# saklar_not_sentuhan.net
KiCad netlist of a schematic drawn in EAGLE
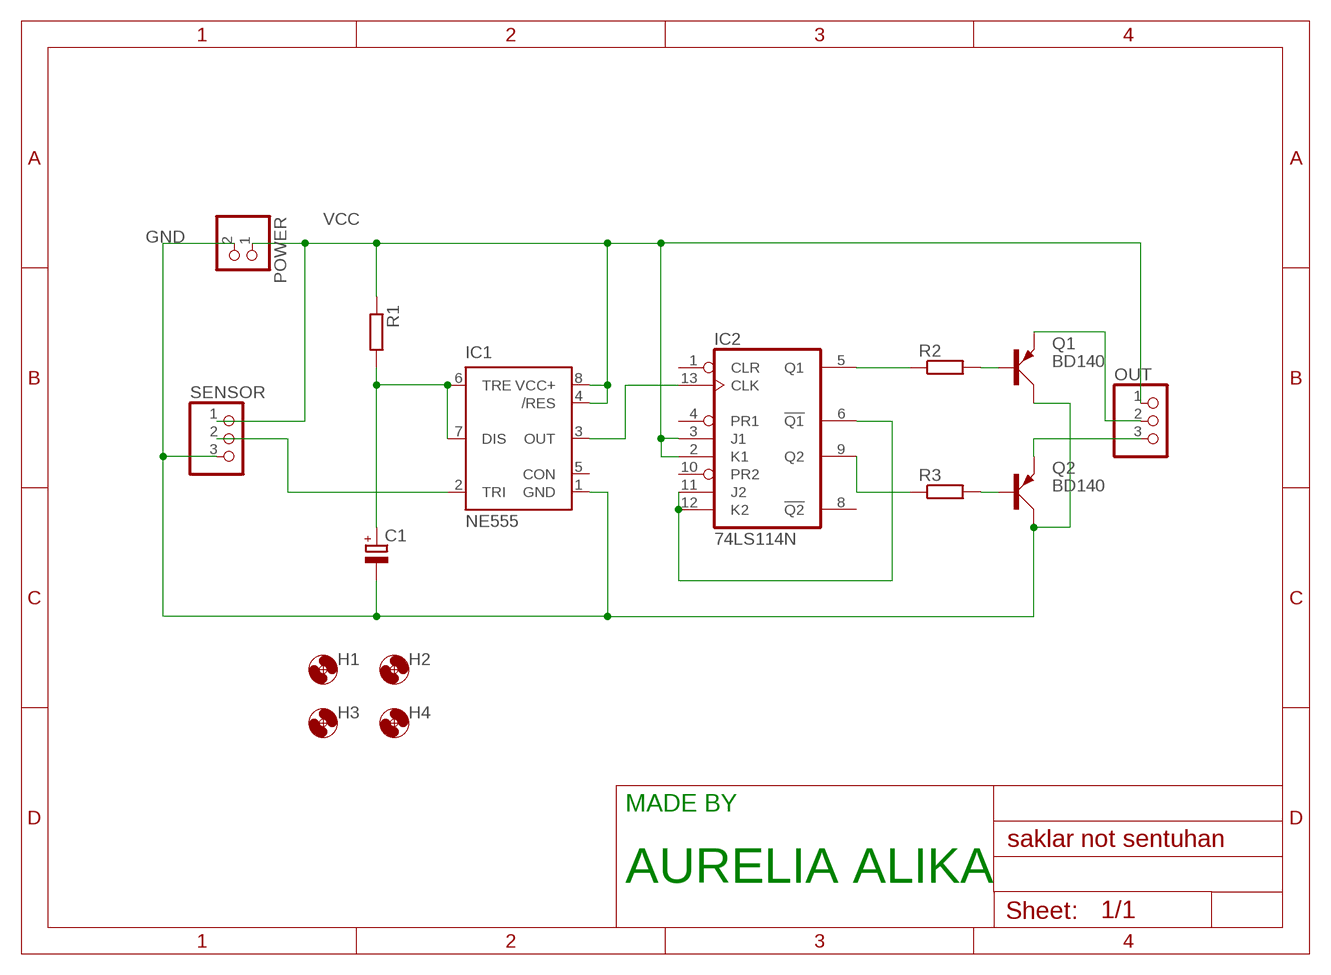
[diagram p0: schematic, sheet 1]

(export (version "E")
  (design (tool "Eeschema 10.0.6"))
  (components
    (comp (ref "C1")
      (value "CPOL-EUE2,5-6E")
      (footprint "eagle-import:E2,5-6E")
      (libsource (lib "eagle-import") (part "CPOL-EUE2,5-6E"))
    )
    (comp (ref "H1")
      (value "MOUNT-HOLE3.6")
      (footprint "eagle-import:3,6")
      (libsource (lib "eagle-import") (part "MOUNT-HOLE3.6"))
    )
    (comp (ref "H2")
      (value "MOUNT-HOLE3.6")
      (footprint "eagle-import:3,6")
      (libsource (lib "eagle-import") (part "MOUNT-HOLE3.6"))
    )
    (comp (ref "H3")
      (value "MOUNT-HOLE3.6")
      (footprint "eagle-import:3,6")
      (libsource (lib "eagle-import") (part "MOUNT-HOLE3.6"))
    )
    (comp (ref "H4")
      (value "MOUNT-HOLE3.6")
      (footprint "eagle-import:3,6")
      (libsource (lib "eagle-import") (part "MOUNT-HOLE3.6"))
    )
    (comp (ref "IC1")
      (value "NE555")
      (footprint "eagle-import:DIL-08")
      (fields (field (name "MF") "Arrow Electronics") (field (name "MPN") "NE555N"))
      (libsource (lib "eagle-import") (part "NE555"))
    )
    (comp (ref "IC2")
      (value "74LS114N")
      (footprint "eagle-import:DIL14")
      (libsource (lib "eagle-import") (part "74114NLS"))
    )
    (comp (ref "OUT")
      (value "PINHD-1X3")
      (footprint "eagle-import:1X03")
      (libsource (lib "eagle-import") (part "PINHD-1X3"))
    )
    (comp (ref "POWER")
      (value "PINHD-1X2")
      (footprint "eagle-import:1X02")
      (libsource (lib "eagle-import") (part "PINHD-1X2"))
    )
    (comp (ref "Q1")
      (value "BD140")
      (footprint "eagle-import:TO126AV")
      (libsource (lib "eagle-import") (part "BD140"))
    )
    (comp (ref "Q2")
      (value "BD140")
      (footprint "eagle-import:TO126AV")
      (libsource (lib "eagle-import") (part "BD140"))
    )
    (comp (ref "R1")
      (value "R-EU_0207/15")
      (footprint "eagle-import:0207_15")
      (libsource (lib "eagle-import") (part "R-EU_0207/15"))
    )
    (comp (ref "R2")
      (value "R-EU_0207/15")
      (footprint "eagle-import:0207_15")
      (libsource (lib "eagle-import") (part "R-EU_0207/15"))
    )
    (comp (ref "R3")
      (value "R-EU_0207/15")
      (footprint "eagle-import:0207_15")
      (libsource (lib "eagle-import") (part "R-EU_0207/15"))
    )
    (comp (ref "SENSOR")
      (value "PINHD-1X3")
      (footprint "eagle-import:1X03")
      (libsource (lib "eagle-import") (part "PINHD-1X3"))
    )
  )
  (nets
    (net (code "1") (name "/GND") (class "Default")
      (node (ref "C1") (pin "-") (pinfunction "-_-") (pintype "passive"))
      (node (ref "IC1") (pin "1") (pinfunction "GND_1") (pintype "power_in"))
      (node (ref "POWER") (pin "2") (pinfunction "2_2") (pintype "passive"))
      (node (ref "Q1") (pin "C") (pinfunction "C_C") (pintype "passive"))
      (node (ref "Q2") (pin "C") (pinfunction "C_C") (pintype "passive"))
      (node (ref "SENSOR") (pin "3") (pinfunction "3_3") (pintype "passive"))
    )
    (net (code "2") (name "/VCC") (class "Default")
      (node (ref "IC1") (pin "4") (pinfunction "/RES_4") (pintype "input"))
      (node (ref "IC1") (pin "8") (pinfunction "VCC+_8") (pintype "power_in"))
      (node (ref "IC2") (pin "2") (pinfunction "K1_2") (pintype "input"))
      (node (ref "IC2") (pin "3") (pinfunction "J1_3") (pintype "input"))
      (node (ref "OUT") (pin "1") (pinfunction "1_1") (pintype "passive"))
      (node (ref "POWER") (pin "1") (pinfunction "1_1") (pintype "passive"))
      (node (ref "R1") (pin "1") (pinfunction "1_1") (pintype "passive"))
      (node (ref "SENSOR") (pin "1") (pinfunction "1_1") (pintype "passive"))
    )
    (net (code "3") (name "Net-(IC1-DIS)") (class "Default")
      (node (ref "C1") (pin "+") (pinfunction "+_+") (pintype "passive"))
      (node (ref "IC1") (pin "6") (pinfunction "TRE_6") (pintype "input"))
      (node (ref "IC1") (pin "7") (pinfunction "DIS_7") (pintype "input"))
      (node (ref "R1") (pin "2") (pinfunction "2_2") (pintype "passive"))
    )
    (net (code "4") (name "Net-(IC1-OUT)") (class "Default")
      (node (ref "IC1") (pin "3") (pinfunction "OUT_3") (pintype "output"))
      (node (ref "IC2") (pin "13") (pinfunction "CLK_13") (pintype "input"))
    )
    (net (code "5") (name "Net-(IC1-TRI)") (class "Default")
      (node (ref "IC1") (pin "2") (pinfunction "TRI_2") (pintype "input"))
      (node (ref "SENSOR") (pin "2") (pinfunction "2_2") (pintype "passive"))
    )
    (net (code "6") (name "Net-(IC2A-J2)") (class "Default")
      (node (ref "IC2") (pin "11") (pinfunction "J2_11") (pintype "input"))
      (node (ref "IC2") (pin "12") (pinfunction "K2_12") (pintype "input"))
      (node (ref "IC2") (pin "6") (pinfunction "~{Q1}_6") (pintype "output"))
    )
    (net (code "7") (name "Net-(IC2A-Q1)") (class "Default")
      (node (ref "IC2") (pin "5") (pinfunction "Q1_5") (pintype "output"))
      (node (ref "R2") (pin "1") (pinfunction "1_1") (pintype "passive"))
    )
    (net (code "8") (name "Net-(IC2A-Q2)") (class "Default")
      (node (ref "IC2") (pin "9") (pinfunction "Q2_9") (pintype "output"))
      (node (ref "R3") (pin "1") (pinfunction "1_1") (pintype "passive"))
    )
    (net (code "9") (name "Net-(OUT-Pad2)") (class "Default")
      (node (ref "OUT") (pin "2") (pinfunction "2_2") (pintype "passive"))
      (node (ref "Q1") (pin "E") (pinfunction "E_E") (pintype "passive"))
    )
    (net (code "10") (name "Net-(OUT-Pad3)") (class "Default")
      (node (ref "OUT") (pin "3") (pinfunction "3_3") (pintype "passive"))
      (node (ref "Q2") (pin "E") (pinfunction "E_E") (pintype "passive"))
    )
    (net (code "11") (name "Net-(Q1-PadB)") (class "Default")
      (node (ref "Q1") (pin "B") (pinfunction "B_B") (pintype "passive"))
      (node (ref "R2") (pin "2") (pinfunction "2_2") (pintype "passive"))
    )
    (net (code "12") (name "Net-(Q2-PadB)") (class "Default")
      (node (ref "Q2") (pin "B") (pinfunction "B_B") (pintype "passive"))
      (node (ref "R3") (pin "2") (pinfunction "2_2") (pintype "passive"))
    )
    (net (code "13") (name "unconnected-(IC1-CON-Pad5)") (class "Default")
      (node (ref "IC1") (pin "5") (pinfunction "CON_5") (pintype "input"))
    )
    (net (code "14") (name "unconnected-(IC2A-CLR-Pad1)") (class "Default")
      (node (ref "IC2") (pin "1") (pinfunction "CLR_1") (pintype "input"))
    )
    (net (code "15") (name "unconnected-(IC2A-PR1-Pad4)") (class "Default")
      (node (ref "IC2") (pin "4") (pinfunction "PR1_4") (pintype "input"))
    )
    (net (code "16") (name "unconnected-(IC2A-PR2-Pad10)") (class "Default")
      (node (ref "IC2") (pin "10") (pinfunction "PR2_10") (pintype "input"))
    )
    (net (code "17") (name "unconnected-(IC2A-~{Q2}-Pad8)") (class "Default")
      (node (ref "IC2") (pin "8") (pinfunction "~{Q2}_8") (pintype "output"))
    )
  )
)
